# laserdot.net
KiCad netlist of a schematic drawn in EAGLE
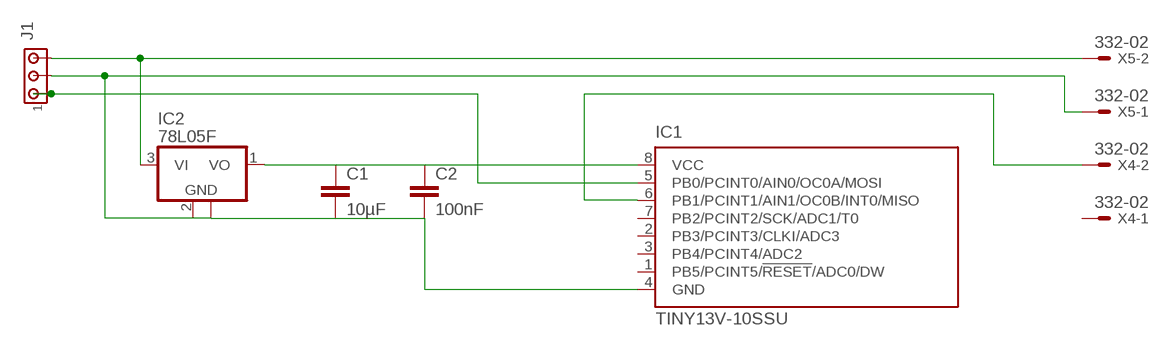
[diagram p0: schematic, sheet 1]

(export (version "E")
  (design (tool "Eeschema 10.0.6"))
  (components
    (comp (ref "C1")
      (value "10µF")
      (footprint "eagle-import:C0805")
      (libsource (lib "eagle-import") (part "C-EUC0805"))
    )
    (comp (ref "C2")
      (value "100nF")
      (footprint "eagle-import:C0805")
      (libsource (lib "eagle-import") (part "C-EUC0805"))
    )
    (comp (ref "IC1")
      (value "TINY13V-10SSU")
      (footprint "eagle-import:8S1")
      (fields (field (name "MPN") "ATTINY13V-10SSU"))
      (libsource (lib "eagle-import") (part "TINY13SSUV-10"))
    )
    (comp (ref "IC2")
      (value "78L05F")
      (footprint "eagle-import:SOT89")
      (libsource (lib "eagle-import") (part "78LF05"))
    )
    (comp (ref "J1")
      (value "MTA03-100")
      (footprint "eagle-import:10X03MTA")
      (libsource (lib "eagle-import") (part "MTA03-100"))
    )
    (comp (ref "X4")
      (value "332-02")
      (footprint "eagle-import:332-02")
      (libsource (lib "eagle-import") (part "332-02"))
    )
    (comp (ref "X5")
      (value "332-02")
      (footprint "eagle-import:332-02")
      (libsource (lib "eagle-import") (part "332-02"))
    )
  )
  (nets
    (net (code "1") (name "Net-(IC1-GND)") (class "Default")
      (node (ref "C1") (pin "2") (pinfunction "2_2") (pintype "passive"))
      (node (ref "C2") (pin "2") (pinfunction "2_2") (pintype "passive"))
      (node (ref "IC1") (pin "4") (pinfunction "GND_4") (pintype "power_in"))
      (node (ref "IC2") (pin "2") (pinfunction "GND_2") (pintype "passive"))
      (node (ref "IC2") (pin "2@1") (pinfunction "GND_2@1") (pintype "passive"))
      (node (ref "J1") (pin "2") (pinfunction "2_2") (pintype "passive"))
      (node (ref "X5") (pin "1") (pinfunction "S_1") (pintype "passive"))
    )
    (net (code "2") (name "Net-(IC1-PB0{slash}PCINT0{slash}AIN0{slash}OC0A{slash}MOSI)") (class "Default")
      (node (ref "IC1") (pin "5") (pinfunction "PB0/PCINT0/AIN0/OC0A/MOSI_5") (pintype "bidirectional"))
      (node (ref "J1") (pin "1") (pinfunction "1_1") (pintype "passive"))
    )
    (net (code "3") (name "Net-(IC1-PB1{slash}PCINT1{slash}AIN1{slash}OC0B{slash}INT0{slash}MISO)") (class "Default")
      (node (ref "IC1") (pin "6") (pinfunction "PB1/PCINT1/AIN1/OC0B/INT0/MISO_6") (pintype "bidirectional"))
      (node (ref "X4") (pin "2") (pinfunction "S_2") (pintype "passive"))
    )
    (net (code "4") (name "Net-(IC1-VCC)") (class "Default")
      (node (ref "C1") (pin "1") (pinfunction "1_1") (pintype "passive"))
      (node (ref "C2") (pin "1") (pinfunction "1_1") (pintype "passive"))
      (node (ref "IC1") (pin "8") (pinfunction "VCC_8") (pintype "power_in"))
      (node (ref "IC2") (pin "1") (pinfunction "VO_1") (pintype "passive"))
    )
    (net (code "5") (name "Net-(IC2-VI)") (class "Default")
      (node (ref "IC2") (pin "3") (pinfunction "VI_3") (pintype "input"))
      (node (ref "J1") (pin "3") (pinfunction "3_3") (pintype "passive"))
      (node (ref "X5") (pin "2") (pinfunction "S_2") (pintype "passive"))
    )
    (net (code "6") (name "unconnected-(IC1-PB2{slash}PCINT2{slash}SCK{slash}ADC1{slash}T0-Pad7)") (class "Default")
      (node (ref "IC1") (pin "7") (pinfunction "PB2/PCINT2/SCK/ADC1/T0_7") (pintype "bidirectional"))
    )
    (net (code "7") (name "unconnected-(IC1-PB3{slash}PCINT3{slash}CLKI{slash}ADC3-Pad2)") (class "Default")
      (node (ref "IC1") (pin "2") (pinfunction "PB3/PCINT3/CLKI/ADC3_2") (pintype "bidirectional"))
    )
    (net (code "8") (name "unconnected-(IC1-PB4{slash}PCINT4{slash}ADC2-Pad3)") (class "Default")
      (node (ref "IC1") (pin "3") (pinfunction "PB4/PCINT4/ADC2_3") (pintype "bidirectional"))
    )
    (net (code "9") (name "unconnected-(IC1-PB5{slash}PCINT5{slash}~{RESET}{slash}ADC0{slash}DW-Pad1)") (class "Default")
      (node (ref "IC1") (pin "1") (pinfunction "PB5/PCINT5/~{RESET}/ADC0/DW_1") (pintype "bidirectional"))
    )
    (net (code "10") (name "unconnected-(X4A-S-Pad1)") (class "Default")
      (node (ref "X4") (pin "1") (pinfunction "S_1") (pintype "passive"))
    )
  )
)
